# EPS_MPPT_XY_Measurements.net
KiCad netlist of a schematic drawn in Altium Designer
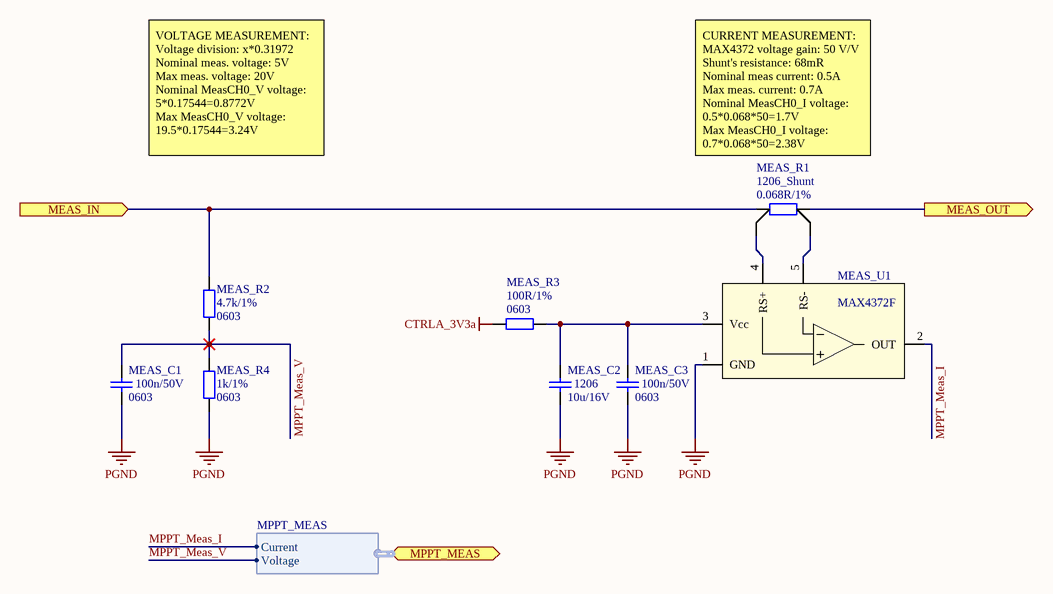
[diagram p0: EPS_MPPT_XY_Measurements.SchDoc]

(export (version "E")
  (design (tool "Eeschema 10.0.6"))
  (components
    (comp (ref "MEAS_C1")
      (value "100n/50V")
      (footprint "SMD_Capacitor_0603")
      (description "Ceramic Cap Kemet COTS 100n/50V X7R 0603")
      (fields
        (field (name "MANUFACTURER") "Kemet")
        (field (name "MANUFACTURERPARTNUMBER") "C0603T104K5RALTU")
        (field (name "PACKAGE") "0603")
      )
      (libsource (lib "capacitors") (part "Cer_C0603T104K5RALTU"))
    )
    (comp (ref "MEAS_C2")
      (value "10u/16V")
      (footprint "SMD_Capacitor_1206")
      (description "Ceramic Cap Kemet COTS 10u/16V X7R 1206")
      (fields
        (field (name "MANUFACTURERPARTNUMBER") "C1206T106K4RACTU")
        (field (name "MANUFACTURER") "Kemet")
        (field (name "PACKGE") "1206")
      )
      (libsource (lib "capacitors") (part "Cer_C1206T106K4RACTU"))
    )
    (comp (ref "MEAS_C3")
      (value "100n/50V")
      (footprint "SMD_Capacitor_0603")
      (description "Ceramic Cap Kemet COTS 100n/50V X7R 0603")
      (fields
        (field (name "MANUFACTURER") "Kemet")
        (field (name "MANUFACTURERPARTNUMBER") "C0603T104K5RALTU")
        (field (name "PACKAGE") "0603")
      )
      (libsource (lib "capacitors") (part "Cer_C0603T104K5RALTU"))
    )
    (comp (ref "MEAS_R1")
      (value "0.068R/1%")
      (footprint "SMD_Resistor-Shunt_1206")
      (description "Panasonic Resistor 68mR 1% 1206 1W")
      (fields
        (field (name "MANUFACTURER") "Panasonic")
        (field (name "MANUFACTURERPARTNUMBER") "ERJ-8BWFR068V")
        (field (name "PACKAGE") "1206_Shunt")
      )
      (libsource (lib "resistors") (part "ERJ-8BWFR068V"))
    )
    (comp (ref "MEAS_R2")
      (value "4.7k/1%")
      (footprint "SMD_Resistor_0603")
      (fields (field (name "PACKAGE") "0603"))
      (libsource (lib "resistors") (part "Res"))
    )
    (comp (ref "MEAS_R3")
      (value "100R/1%")
      (footprint "SMD_Resistor_0603")
      (fields (field (name "PACKAGE") "0603"))
      (libsource (lib "") (part "Res_1"))
    )
    (comp (ref "MEAS_R4")
      (value "1k/1%")
      (footprint "SMD_Resistor_0603")
      (fields (field (name "PACKAGE") "0603"))
      (libsource (lib "resistors") (part "Res"))
    )
    (comp (ref "MEAS_U1")
      (value "MAX4372F")
      (footprint "SOT23-5")
      (description "High-Side Current-Sense Amplifier with Voltage Output")
      (fields (field (name "MANUFACTURER") "Maxim Integrated Products"))
      (libsource (lib "microcircuits") (part "MAX4372"))
    )
  )
  (nets
    (net (code "2") (name "/MEAS_IN") (class "Default")
      (node (ref "MEAS_R1") (pin "1") (pinfunction "1_1") (pintype "passive"))
      (node (ref "MEAS_R2") (pin "1") (pinfunction "1_1") (pintype "passive"))
    )
    (net (code "3") (name "/MEAS_OUT") (class "Default")
      (node (ref "MEAS_R1") (pin "4") (pinfunction "4_4") (pintype "passive"))
    )
    (net (code "4") (name "/MPPT_Meas_I") (class "Default")
      (node (ref "MEAS_U1") (pin "2") (pinfunction "OUT_2") (pintype "passive"))
    )
    (net (code "5") (name "/MPPT_Meas_V") (class "Default")
      (node (ref "MEAS_C1") (pin "1") (pinfunction "1_1") (pintype "passive"))
      (node (ref "MEAS_R2") (pin "2") (pinfunction "2_2") (pintype "passive"))
      (node (ref "MEAS_R4") (pin "1") (pinfunction "1_1") (pintype "passive"))
    )
    (net (code "7") (name "CTRLA_3V3a") (class "Default")
      (node (ref "MEAS_R3") (pin "1") (pinfunction "1_1") (pintype "passive"))
    )
    (net (code "8") (name "Net-(MEAS_U1-RS+)") (class "Default")
      (node (ref "MEAS_R1") (pin "2") (pinfunction "2_2") (pintype "passive"))
      (node (ref "MEAS_U1") (pin "4") (pinfunction "RS+_4") (pintype "passive"))
    )
    (net (code "9") (name "Net-(MEAS_U1-RS-)") (class "Default")
      (node (ref "MEAS_R1") (pin "3") (pinfunction "3_3") (pintype "passive"))
      (node (ref "MEAS_U1") (pin "5") (pinfunction "RS-_5") (pintype "passive"))
    )
    (net (code "10") (name "Net-(MEAS_U1-Vcc)") (class "Default")
      (node (ref "MEAS_C2") (pin "1") (pinfunction "1_1") (pintype "passive"))
      (node (ref "MEAS_C3") (pin "1") (pinfunction "1_1") (pintype "passive"))
      (node (ref "MEAS_R3") (pin "2") (pinfunction "2_2") (pintype "passive"))
      (node (ref "MEAS_U1") (pin "3") (pinfunction "Vcc_3") (pintype "passive"))
    )
    (net (code "11") (name "PGND") (class "Default")
      (node (ref "MEAS_C1") (pin "2") (pinfunction "2_2") (pintype "passive"))
      (node (ref "MEAS_C2") (pin "2") (pinfunction "2_2") (pintype "passive"))
      (node (ref "MEAS_C3") (pin "2") (pinfunction "2_2") (pintype "passive"))
      (node (ref "MEAS_R4") (pin "2") (pinfunction "2_2") (pintype "passive"))
      (node (ref "MEAS_U1") (pin "1") (pinfunction "GND_1") (pintype "passive"))
    )
  )
)
